# S5_Communications.net
KiCad netlist of a schematic drawn in Altium Designer
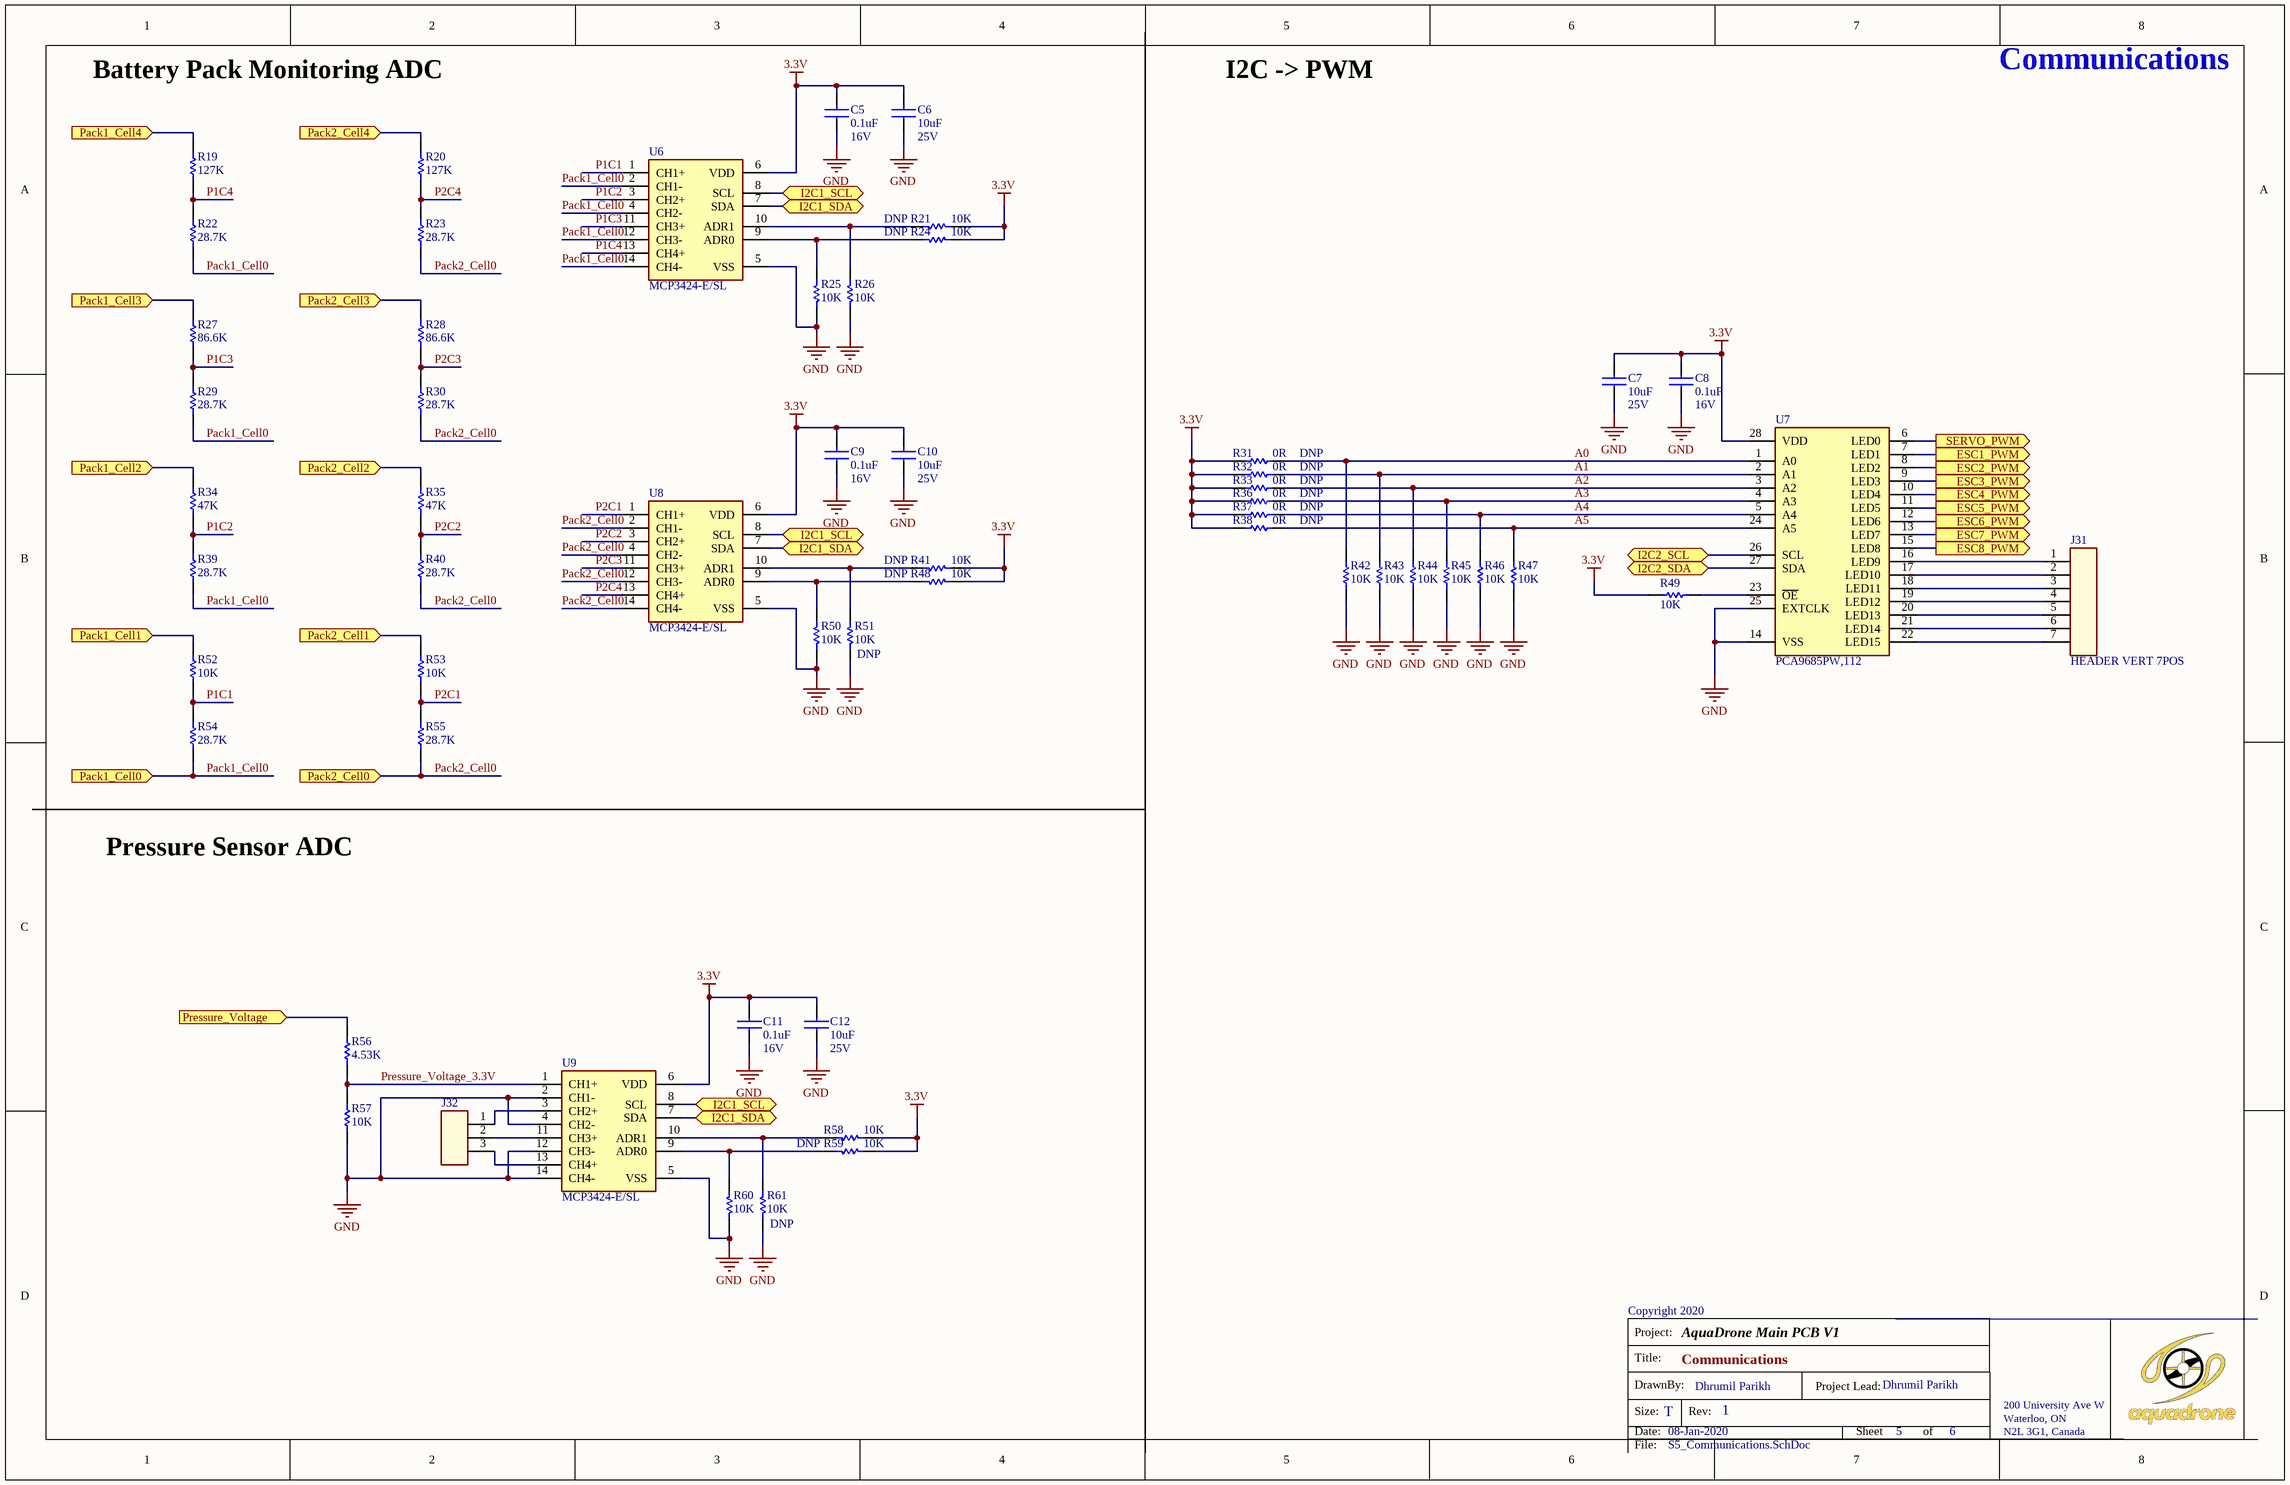
[diagram p0: S5_Communications.SchDoc]

(export (version "E")
  (design (tool "Eeschema 10.0.6"))
  (components
    (comp (ref "C5")
      (value "0.1uF")
      (footprint "RWMN:CAPC1608X09N")
      (description "CAP CER 0.1UF 16V X7R 0603")
      (fields
        (field (name "MFG") "KEMET")
        (field (name "MFG_PART_NO") "C0603C104M4RACTU")
        (field (name "VOLTAGE") "16V")
      )
      (libsource (lib "AquaDrone") (part "CAP CER 0.1UF 16V X7R 0603"))
    )
    (comp (ref "C6")
      (value "10uF")
      (footprint "RWMN:CAPC1608X09N")
      (description "CAP CER 10UF 25V X5R 0603")
      (fields
        (field (name "MFG") "KEMET")
        (field (name "MFG_PART_NO") "C1608X5R1E106M080AC")
        (field (name "VOLTAGE") "25V")
      )
      (libsource (lib "AquaDrone") (part "CAP CER 10UF 25V X5R 0603"))
    )
    (comp (ref "C7")
      (value "10uF")
      (footprint "RWMN:CAPC1608X09N")
      (description "CAP CER 10UF 25V X5R 0603")
      (fields
        (field (name "MFG") "KEMET")
        (field (name "MFG_PART_NO") "C1608X5R1E106M080AC")
        (field (name "VOLTAGE") "25V")
      )
      (libsource (lib "AquaDrone") (part "CAP CER 10UF 25V X5R 0603"))
    )
    (comp (ref "C8")
      (value "0.1uF")
      (footprint "RWMN:CAPC1608X09N")
      (description "CAP CER 0.1UF 16V X7R 0603")
      (fields
        (field (name "MFG") "KEMET")
        (field (name "MFG_PART_NO") "C0603C104M4RACTU")
        (field (name "VOLTAGE") "16V")
      )
      (libsource (lib "AquaDrone") (part "CAP CER 0.1UF 16V X7R 0603"))
    )
    (comp (ref "C9")
      (value "0.1uF")
      (footprint "RWMN:CAPC1608X09N")
      (description "CAP CER 0.1UF 16V X7R 0603")
      (fields
        (field (name "MFG") "KEMET")
        (field (name "MFG_PART_NO") "C0603C104M4RACTU")
        (field (name "VOLTAGE") "16V")
      )
      (libsource (lib "AquaDrone") (part "CAP CER 0.1UF 16V X7R 0603"))
    )
    (comp (ref "C10")
      (value "10uF")
      (footprint "RWMN:CAPC1608X09N")
      (description "CAP CER 10UF 25V X5R 0603")
      (fields
        (field (name "MFG") "KEMET")
        (field (name "MFG_PART_NO") "C1608X5R1E106M080AC")
        (field (name "VOLTAGE") "25V")
      )
      (libsource (lib "AquaDrone") (part "CAP CER 10UF 25V X5R 0603"))
    )
    (comp (ref "C11")
      (value "0.1uF")
      (footprint "RWMN:CAPC1608X09N")
      (description "CAP CER 0.1UF 16V X7R 0603")
      (fields
        (field (name "MFG") "KEMET")
        (field (name "MFG_PART_NO") "C0603C104M4RACTU")
        (field (name "VOLTAGE") "16V")
      )
      (libsource (lib "AquaDrone") (part "CAP CER 0.1UF 16V X7R 0603"))
    )
    (comp (ref "C12")
      (value "10uF")
      (footprint "RWMN:CAPC1608X09N")
      (description "CAP CER 10UF 25V X5R 0603")
      (fields
        (field (name "MFG") "KEMET")
        (field (name "MFG_PART_NO") "C1608X5R1E106M080AC")
        (field (name "VOLTAGE") "25V")
      )
      (libsource (lib "AquaDrone") (part "CAP CER 10UF 25V X5R 0603"))
    )
    (comp (ref "J31")
      (value "HEADER VERT 7POS")
      (footprint "61300711121")
      (description "CONN HEADER VERT 7POS 2.54MM")
      (fields (field (name "MFG") "Wurth Electronics Inc.") (field (name "MFG_PART_NO") "61300711121"))
      (libsource (lib "AquaDrone") (part "CONN HEADER VERT 7POS 2.54MM"))
    )
    (comp (ref "J32")
      (value "CONN HEADER VERT 3POS 2.54MM")
      (footprint "RWMN:61300311121")
      (fields (field (name "MFG") "Wurth Electronics Inc.") (field (name "MFG_PART_NO") "61300311121"))
      (libsource (lib "AquaDrone") (part "CONN HEADER VERT 3POS 2.54MM"))
    )
    (comp (ref "R19")
      (value "127K")
      (footprint "RESC1608X06N")
      (description "RES SMD 127K OHM 1% 1/10W 0603")
      (fields (field (name "MFG") "Vishay Dale") (field (name "MFG_PART_NO") "CRCW0603127KFKEA"))
      (libsource (lib "AquaDrone") (part "RES SMD 127K OHM 1% 1/10W 0603"))
    )
    (comp (ref "R20")
      (value "127K")
      (footprint "RESC1608X06N")
      (description "RES SMD 127K OHM 1% 1/10W 0603")
      (fields (field (name "MFG") "Vishay Dale") (field (name "MFG_PART_NO") "CRCW0603127KFKEA"))
      (libsource (lib "AquaDrone") (part "RES SMD 127K OHM 1% 1/10W 0603"))
    )
    (comp (ref "R21")
      (value "10K")
      (footprint "RESC1608X06N")
      (description "RES SMD 10K OHM 1% 1/10W 0603")
      (fields
        (field (name "MFG") "Vishay Dale")
        (field (name "NOSTUFF") "DNP")
        (field (name "MFG_PART_NO") "CRCW060310K0FKEA")
      )
      (libsource (lib "AquaDrone") (part "RES SMD 10K OHM 1% 1/10W 0603"))
    )
    (comp (ref "R22")
      (value "28.7K")
      (footprint "RESC1608X06N")
      (description "RES SMD 28.7K OHM 1% 1/10W 0603")
      (fields (field (name "MFG") "Yageo") (field (name "MFG_PART_NO") "RC0603FR-0728K7L"))
      (libsource (lib "AquaDrone") (part "RES SMD 28.7K OHM 1% 1/10W 0603"))
    )
    (comp (ref "R23")
      (value "28.7K")
      (footprint "RESC1608X06N")
      (description "RES SMD 28.7K OHM 1% 1/10W 0603")
      (fields (field (name "MFG") "Yageo") (field (name "MFG_PART_NO") "RC0603FR-0728K7L"))
      (libsource (lib "AquaDrone") (part "RES SMD 28.7K OHM 1% 1/10W 0603"))
    )
    (comp (ref "R24")
      (value "10K")
      (footprint "RESC1608X06N")
      (description "RES SMD 10K OHM 1% 1/10W 0603")
      (fields
        (field (name "MFG") "Vishay Dale")
        (field (name "NOSTUFF") "DNP")
        (field (name "MFG_PART_NO") "CRCW060310K0FKEA")
      )
      (libsource (lib "AquaDrone") (part "RES SMD 10K OHM 1% 1/10W 0603"))
    )
    (comp (ref "R25")
      (value "10K")
      (footprint "RESC1608X06N")
      (description "RES SMD 10K OHM 1% 1/10W 0603")
      (fields (field (name "MFG") "Vishay Dale") (field (name "MFG_PART_NO") "CRCW060310K0FKEA"))
      (libsource (lib "AquaDrone") (part "RES SMD 10K OHM 1% 1/10W 0603"))
    )
    (comp (ref "R26")
      (value "10K")
      (footprint "RESC1608X06N")
      (description "RES SMD 10K OHM 1% 1/10W 0603")
      (fields (field (name "MFG") "Vishay Dale") (field (name "MFG_PART_NO") "CRCW060310K0FKEA"))
      (libsource (lib "AquaDrone") (part "RES SMD 10K OHM 1% 1/10W 0603"))
    )
    (comp (ref "R27")
      (value "86.6K")
      (footprint "RESC1608X06N")
      (description "RES SMD 86.6K OHM 1% 1/10W 0603")
      (fields (field (name "MFG") "Yageo") (field (name "MFG_PART_NO") "RC0603FR-0786K6L"))
      (libsource (lib "AquaDrone") (part "RES SMD 86.6K OHM 1% 1/10W 0603"))
    )
    (comp (ref "R28")
      (value "86.6K")
      (footprint "RESC1608X06N")
      (description "RES SMD 86.6K OHM 1% 1/10W 0603")
      (fields (field (name "MFG") "Yageo") (field (name "MFG_PART_NO") "RC0603FR-0786K6L"))
      (libsource (lib "AquaDrone") (part "RES SMD 86.6K OHM 1% 1/10W 0603"))
    )
    (comp (ref "R29")
      (value "28.7K")
      (footprint "RESC1608X06N")
      (description "RES SMD 28.7K OHM 1% 1/10W 0603")
      (fields (field (name "MFG") "Yageo") (field (name "MFG_PART_NO") "RC0603FR-0728K7L"))
      (libsource (lib "AquaDrone") (part "RES SMD 28.7K OHM 1% 1/10W 0603"))
    )
    (comp (ref "R30")
      (value "28.7K")
      (footprint "RESC1608X06N")
      (description "RES SMD 28.7K OHM 1% 1/10W 0603")
      (fields (field (name "MFG") "Yageo") (field (name "MFG_PART_NO") "RC0603FR-0728K7L"))
      (libsource (lib "AquaDrone") (part "RES SMD 28.7K OHM 1% 1/10W 0603"))
    )
    (comp (ref "R31")
      (value "0R")
      (footprint "RESC2012X07N")
      (description "RES SMD 0 OHM JUMPER 1/8W 0805")
      (fields
        (field (name "MFG") "Panasonic")
        (field (name "NOSTUFF") "DNP")
        (field (name "MFG_PART_NO") "ERJ-6GEY0R00V")
      )
      (libsource (lib "AquaDrone") (part "RES SMD 0 OHM JUMPER 1/8W 0805"))
    )
    (comp (ref "R32")
      (value "0R")
      (footprint "RESC2012X07N")
      (description "RES SMD 0 OHM JUMPER 1/8W 0805")
      (fields
        (field (name "MFG") "Panasonic")
        (field (name "NOSTUFF") "DNP")
        (field (name "MFG_PART_NO") "ERJ-6GEY0R00V")
      )
      (libsource (lib "AquaDrone") (part "RES SMD 0 OHM JUMPER 1/8W 0805"))
    )
    (comp (ref "R33")
      (value "0R")
      (footprint "RESC2012X07N")
      (description "RES SMD 0 OHM JUMPER 1/8W 0805")
      (fields
        (field (name "MFG") "Panasonic")
        (field (name "NOSTUFF") "DNP")
        (field (name "MFG_PART_NO") "ERJ-6GEY0R00V")
      )
      (libsource (lib "AquaDrone") (part "RES SMD 0 OHM JUMPER 1/8W 0805"))
    )
    (comp (ref "R34")
      (value "47K")
      (footprint "RESC1608X06N")
      (description "RES SMD 47K OHM 1% 1/10W 0603")
      (fields (field (name "MFG") "Yageo") (field (name "MFG_PART_NO") "RC0603FR-0747KL"))
      (libsource (lib "AquaDrone") (part "RES SMD 47K OHM 1% 1/10W 0603"))
    )
    (comp (ref "R35")
      (value "47K")
      (footprint "RESC1608X06N")
      (description "RES SMD 47K OHM 1% 1/10W 0603")
      (fields (field (name "MFG") "Yageo") (field (name "MFG_PART_NO") "RC0603FR-0747KL"))
      (libsource (lib "AquaDrone") (part "RES SMD 47K OHM 1% 1/10W 0603"))
    )
    (comp (ref "R36")
      (value "0R")
      (footprint "RESC2012X07N")
      (description "RES SMD 0 OHM JUMPER 1/8W 0805")
      (fields
        (field (name "MFG") "Panasonic")
        (field (name "NOSTUFF") "DNP")
        (field (name "MFG_PART_NO") "ERJ-6GEY0R00V")
      )
      (libsource (lib "AquaDrone") (part "RES SMD 0 OHM JUMPER 1/8W 0805"))
    )
    (comp (ref "R37")
      (value "0R")
      (footprint "RESC2012X07N")
      (description "RES SMD 0 OHM JUMPER 1/8W 0805")
      (fields
        (field (name "MFG") "Panasonic")
        (field (name "NOSTUFF") "DNP")
        (field (name "MFG_PART_NO") "ERJ-6GEY0R00V")
      )
      (libsource (lib "AquaDrone") (part "RES SMD 0 OHM JUMPER 1/8W 0805"))
    )
    (comp (ref "R38")
      (value "0R")
      (footprint "RESC2012X07N")
      (description "RES SMD 0 OHM JUMPER 1/8W 0805")
      (fields
        (field (name "MFG") "Panasonic")
        (field (name "NOSTUFF") "DNP")
        (field (name "MFG_PART_NO") "ERJ-6GEY0R00V")
      )
      (libsource (lib "AquaDrone") (part "RES SMD 0 OHM JUMPER 1/8W 0805"))
    )
    (comp (ref "R39")
      (value "28.7K")
      (footprint "RESC1608X06N")
      (description "RES SMD 28.7K OHM 1% 1/10W 0603")
      (fields (field (name "MFG") "Yageo") (field (name "MFG_PART_NO") "RC0603FR-0728K7L"))
      (libsource (lib "AquaDrone") (part "RES SMD 28.7K OHM 1% 1/10W 0603"))
    )
    (comp (ref "R40")
      (value "28.7K")
      (footprint "RESC1608X06N")
      (description "RES SMD 28.7K OHM 1% 1/10W 0603")
      (fields (field (name "MFG") "Yageo") (field (name "MFG_PART_NO") "RC0603FR-0728K7L"))
      (libsource (lib "AquaDrone") (part "RES SMD 28.7K OHM 1% 1/10W 0603"))
    )
    (comp (ref "R41")
      (value "10K")
      (footprint "RESC1608X06N")
      (description "RES SMD 10K OHM 1% 1/10W 0603")
      (fields
        (field (name "MFG") "Vishay Dale")
        (field (name "NOSTUFF") "DNP")
        (field (name "MFG_PART_NO") "CRCW060310K0FKEA")
      )
      (libsource (lib "AquaDrone") (part "RES SMD 10K OHM 1% 1/10W 0603"))
    )
    (comp (ref "R42")
      (value "10K")
      (footprint "RESC1608X06N")
      (description "RES SMD 10K OHM 1% 1/10W 0603")
      (fields (field (name "MFG") "Vishay Dale") (field (name "MFG_PART_NO") "CRCW060310K0FKEA"))
      (libsource (lib "AquaDrone") (part "RES SMD 10K OHM 1% 1/10W 0603"))
    )
    (comp (ref "R43")
      (value "10K")
      (footprint "RESC1608X06N")
      (description "RES SMD 10K OHM 1% 1/10W 0603")
      (fields (field (name "MFG") "Vishay Dale") (field (name "MFG_PART_NO") "CRCW060310K0FKEA"))
      (libsource (lib "AquaDrone") (part "RES SMD 10K OHM 1% 1/10W 0603"))
    )
    (comp (ref "R44")
      (value "10K")
      (footprint "RESC1608X06N")
      (description "RES SMD 10K OHM 1% 1/10W 0603")
      (fields (field (name "MFG") "Vishay Dale") (field (name "MFG_PART_NO") "CRCW060310K0FKEA"))
      (libsource (lib "AquaDrone") (part "RES SMD 10K OHM 1% 1/10W 0603"))
    )
    (comp (ref "R45")
      (value "10K")
      (footprint "RESC1608X06N")
      (description "RES SMD 10K OHM 1% 1/10W 0603")
      (fields (field (name "MFG") "Vishay Dale") (field (name "MFG_PART_NO") "CRCW060310K0FKEA"))
      (libsource (lib "AquaDrone") (part "RES SMD 10K OHM 1% 1/10W 0603"))
    )
    (comp (ref "R46")
      (value "10K")
      (footprint "RESC1608X06N")
      (description "RES SMD 10K OHM 1% 1/10W 0603")
      (fields (field (name "MFG") "Vishay Dale") (field (name "MFG_PART_NO") "CRCW060310K0FKEA"))
      (libsource (lib "AquaDrone") (part "RES SMD 10K OHM 1% 1/10W 0603"))
    )
    (comp (ref "R47")
      (value "10K")
      (footprint "RESC1608X06N")
      (description "RES SMD 10K OHM 1% 1/10W 0603")
      (fields (field (name "MFG") "Vishay Dale") (field (name "MFG_PART_NO") "CRCW060310K0FKEA"))
      (libsource (lib "AquaDrone") (part "RES SMD 10K OHM 1% 1/10W 0603"))
    )
    (comp (ref "R48")
      (value "10K")
      (footprint "RESC1608X06N")
      (description "RES SMD 10K OHM 1% 1/10W 0603")
      (fields
        (field (name "MFG") "Vishay Dale")
        (field (name "NOSTUFF") "DNP")
        (field (name "MFG_PART_NO") "CRCW060310K0FKEA")
      )
      (libsource (lib "AquaDrone") (part "RES SMD 10K OHM 1% 1/10W 0603"))
    )
    (comp (ref "R49")
      (value "10K")
      (footprint "RESC1608X06N")
      (description "RES SMD 10K OHM 1% 1/10W 0603")
      (fields (field (name "MFG") "Vishay Dale") (field (name "MFG_PART_NO") "CRCW060310K0FKEA"))
      (libsource (lib "AquaDrone") (part "RES SMD 10K OHM 1% 1/10W 0603"))
    )
    (comp (ref "R50")
      (value "10K")
      (footprint "RESC1608X06N")
      (description "RES SMD 10K OHM 1% 1/10W 0603")
      (fields (field (name "MFG") "Vishay Dale") (field (name "MFG_PART_NO") "CRCW060310K0FKEA"))
      (libsource (lib "AquaDrone") (part "RES SMD 10K OHM 1% 1/10W 0603"))
    )
    (comp (ref "R51")
      (value "10K")
      (footprint "RESC1608X06N")
      (description "RES SMD 10K OHM 1% 1/10W 0603")
      (fields
        (field (name "MFG") "Vishay Dale")
        (field (name "NOSTUFF") "DNP")
        (field (name "MFG_PART_NO") "CRCW060310K0FKEA")
      )
      (libsource (lib "AquaDrone") (part "RES SMD 10K OHM 1% 1/10W 0603"))
    )
    (comp (ref "R52")
      (value "10K")
      (footprint "RESC1608X06N")
      (description "RES SMD 10K OHM 1% 1/10W 0603")
      (fields (field (name "MFG") "Vishay Dale") (field (name "MFG_PART_NO") "CRCW060310K0FKEA"))
      (libsource (lib "AquaDrone") (part "RES SMD 10K OHM 1% 1/10W 0603"))
    )
    (comp (ref "R53")
      (value "10K")
      (footprint "RESC1608X06N")
      (description "RES SMD 10K OHM 1% 1/10W 0603")
      (fields (field (name "MFG") "Vishay Dale") (field (name "MFG_PART_NO") "CRCW060310K0FKEA"))
      (libsource (lib "AquaDrone") (part "RES SMD 10K OHM 1% 1/10W 0603"))
    )
    (comp (ref "R54")
      (value "28.7K")
      (footprint "RESC1608X06N")
      (description "RES SMD 28.7K OHM 1% 1/10W 0603")
      (fields (field (name "MFG") "Yageo") (field (name "MFG_PART_NO") "RC0603FR-0728K7L"))
      (libsource (lib "AquaDrone") (part "RES SMD 28.7K OHM 1% 1/10W 0603"))
    )
    (comp (ref "R55")
      (value "28.7K")
      (footprint "RESC1608X06N")
      (description "RES SMD 28.7K OHM 1% 1/10W 0603")
      (fields (field (name "MFG") "Yageo") (field (name "MFG_PART_NO") "RC0603FR-0728K7L"))
      (libsource (lib "AquaDrone") (part "RES SMD 28.7K OHM 1% 1/10W 0603"))
    )
    (comp (ref "R56")
      (value "4.53K")
      (footprint "RESC1608X06N")
      (description "RES SMD 4.53K OHM 1% 1/10W 0603")
      (fields (field (name "MFG") "Yageo") (field (name "MFG_PART_NO") "RC0603FR-074K53L"))
      (libsource (lib "AquaDrone") (part "RES SMD 4.53K OHM 1% 1/10W 0603"))
    )
    (comp (ref "R57")
      (value "10K")
      (footprint "RESC1608X06N")
      (description "RES SMD 10K OHM 1% 1/10W 0603")
      (fields (field (name "MFG") "Vishay Dale") (field (name "MFG_PART_NO") "CRCW060310K0FKEA"))
      (libsource (lib "AquaDrone") (part "RES SMD 10K OHM 1% 1/10W 0603"))
    )
    (comp (ref "R58")
      (value "10K")
      (footprint "RESC1608X06N")
      (description "RES SMD 10K OHM 1% 1/10W 0603")
      (fields (field (name "MFG") "Vishay Dale") (field (name "MFG_PART_NO") "CRCW060310K0FKEA"))
      (libsource (lib "AquaDrone") (part "RES SMD 10K OHM 1% 1/10W 0603"))
    )
    (comp (ref "R59")
      (value "10K")
      (footprint "RESC1608X06N")
      (description "RES SMD 10K OHM 1% 1/10W 0603")
      (fields
        (field (name "MFG") "Vishay Dale")
        (field (name "NOSTUFF") "DNP")
        (field (name "MFG_PART_NO") "CRCW060310K0FKEA")
      )
      (libsource (lib "AquaDrone") (part "RES SMD 10K OHM 1% 1/10W 0603"))
    )
    (comp (ref "R60")
      (value "10K")
      (footprint "RESC1608X06N")
      (description "RES SMD 10K OHM 1% 1/10W 0603")
      (fields (field (name "MFG") "Vishay Dale") (field (name "MFG_PART_NO") "CRCW060310K0FKEA"))
      (libsource (lib "AquaDrone") (part "RES SMD 10K OHM 1% 1/10W 0603"))
    )
    (comp (ref "R61")
      (value "10K")
      (footprint "RESC1608X06N")
      (description "RES SMD 10K OHM 1% 1/10W 0603")
      (fields
        (field (name "MFG") "Vishay Dale")
        (field (name "NOSTUFF") "DNP")
        (field (name "MFG_PART_NO") "CRCW060310K0FKEA")
      )
      (libsource (lib "AquaDrone") (part "RES SMD 10K OHM 1% 1/10W 0603"))
    )
    (comp (ref "U6")
      (value "IC ADC 18BIT SIGMA-DELTA 14SOIC")
      (footprint "SOIC127P600X175-14N")
      (fields (field (name "MFG") "Microchip Technology") (field (name "MFG_PART_NO") "MCP3424-E/SL"))
      (libsource (lib "AquaDrone") (part "IC ADC 18BIT SIGMA-DELTA 14SOIC"))
    )
    (comp (ref "U7")
      (value "IC LED DRVR LIN DIM 25MA 28TSSOP")
      (footprint "SOP65P640X110-28N")
      (fields (field (name "MFG") "NXP USA Inc.") (field (name "MFG_PART_NO") "PCA9685PW,112"))
      (libsource (lib "AquaDrone") (part "IC LED DRVR LIN DIM 25MA 28TSSOP"))
    )
    (comp (ref "U8")
      (value "IC ADC 18BIT SIGMA-DELTA 14SOIC")
      (footprint "SOIC127P600X175-14N")
      (fields (field (name "MFG") "Microchip Technology") (field (name "MFG_PART_NO") "MCP3424-E/SL"))
      (libsource (lib "AquaDrone") (part "IC ADC 18BIT SIGMA-DELTA 14SOIC"))
    )
    (comp (ref "U9")
      (value "IC ADC 18BIT SIGMA-DELTA 14SOIC")
      (footprint "SOIC127P600X175-14N")
      (fields (field (name "MFG") "Microchip Technology") (field (name "MFG_PART_NO") "MCP3424-E/SL"))
      (libsource (lib "AquaDrone") (part "IC ADC 18BIT SIGMA-DELTA 14SOIC"))
    )
  )
  (nets
    (net (code "1") (name "/A0") (class "Default")
      (node (ref "R31") (pin "2") (pinfunction "2_2") (pintype "passive"))
      (node (ref "R42") (pin "2") (pinfunction "2_2") (pintype "passive"))
      (node (ref "U7") (pin "1") (pinfunction "A0_1") (pintype "passive"))
    )
    (net (code "2") (name "/A1") (class "Default")
      (node (ref "R32") (pin "2") (pinfunction "2_2") (pintype "passive"))
      (node (ref "R43") (pin "2") (pinfunction "2_2") (pintype "passive"))
      (node (ref "U7") (pin "2") (pinfunction "A1_2") (pintype "passive"))
    )
    (net (code "3") (name "/A2") (class "Default")
      (node (ref "R33") (pin "2") (pinfunction "2_2") (pintype "passive"))
      (node (ref "R44") (pin "2") (pinfunction "2_2") (pintype "passive"))
      (node (ref "U7") (pin "3") (pinfunction "A2_3") (pintype "passive"))
    )
    (net (code "4") (name "/A3") (class "Default")
      (node (ref "R36") (pin "2") (pinfunction "2_2") (pintype "passive"))
      (node (ref "R45") (pin "2") (pinfunction "2_2") (pintype "passive"))
      (node (ref "U7") (pin "4") (pinfunction "A3_4") (pintype "passive"))
    )
    (net (code "5") (name "/A4") (class "Default")
      (node (ref "R37") (pin "2") (pinfunction "2_2") (pintype "passive"))
      (node (ref "R46") (pin "2") (pinfunction "2_2") (pintype "passive"))
      (node (ref "U7") (pin "5") (pinfunction "A4_5") (pintype "passive"))
    )
    (net (code "6") (name "/A5") (class "Default")
      (node (ref "R38") (pin "2") (pinfunction "2_2") (pintype "passive"))
      (node (ref "R47") (pin "2") (pinfunction "2_2") (pintype "passive"))
      (node (ref "U7") (pin "24") (pinfunction "A5_24") (pintype "passive"))
    )
    (net (code "7") (name "/ESC1_PWM") (class "Default")
      (node (ref "U7") (pin "7") (pinfunction "LED1_7") (pintype "passive"))
    )
    (net (code "8") (name "/ESC2_PWM") (class "Default")
      (node (ref "U7") (pin "8") (pinfunction "LED2_8") (pintype "passive"))
    )
    (net (code "9") (name "/ESC3_PWM") (class "Default")
      (node (ref "U7") (pin "9") (pinfunction "LED3_9") (pintype "passive"))
    )
    (net (code "10") (name "/ESC4_PWM") (class "Default")
      (node (ref "U7") (pin "10") (pinfunction "LED4_10") (pintype "passive"))
    )
    (net (code "11") (name "/ESC5_PWM") (class "Default")
      (node (ref "U7") (pin "11") (pinfunction "LED5_11") (pintype "passive"))
    )
    (net (code "12") (name "/ESC6_PWM") (class "Default")
      (node (ref "U7") (pin "12") (pinfunction "LED6_12") (pintype "passive"))
    )
    (net (code "13") (name "/ESC7_PWM") (class "Default")
      (node (ref "U7") (pin "13") (pinfunction "LED7_13") (pintype "passive"))
    )
    (net (code "14") (name "/ESC8_PWM") (class "Default")
      (node (ref "U7") (pin "15") (pinfunction "LED8_15") (pintype "passive"))
    )
    (net (code "15") (name "/I2C1_SCL") (class "Default")
      (node (ref "U6") (pin "8") (pinfunction "SCL_8") (pintype "passive"))
      (node (ref "U8") (pin "8") (pinfunction "SCL_8") (pintype "passive"))
      (node (ref "U9") (pin "8") (pinfunction "SCL_8") (pintype "passive"))
    )
    (net (code "16") (name "/I2C1_SDA") (class "Default")
      (node (ref "U6") (pin "7") (pinfunction "SDA_7") (pintype "passive"))
      (node (ref "U8") (pin "7") (pinfunction "SDA_7") (pintype "passive"))
      (node (ref "U9") (pin "7") (pinfunction "SDA_7") (pintype "passive"))
    )
    (net (code "17") (name "/I2C2_SCL") (class "Default")
      (node (ref "U7") (pin "26") (pinfunction "SCL_26") (pintype "passive"))
    )
    (net (code "18") (name "/I2C2_SDA") (class "Default")
      (node (ref "U7") (pin "27") (pinfunction "SDA_27") (pintype "passive"))
    )
    (net (code "19") (name "/P1C1") (class "Default")
      (node (ref "R52") (pin "1") (pinfunction "1_1") (pintype "passive"))
      (node (ref "R54") (pin "2") (pinfunction "2_2") (pintype "passive"))
      (node (ref "U6") (pin "1") (pinfunction "CH1+_1") (pintype "passive"))
    )
    (net (code "20") (name "/P1C2") (class "Default")
      (node (ref "R34") (pin "1") (pinfunction "1_1") (pintype "passive"))
      (node (ref "R39") (pin "2") (pinfunction "2_2") (pintype "passive"))
      (node (ref "U6") (pin "3") (pinfunction "CH2+_3") (pintype "passive"))
    )
    (net (code "21") (name "/P1C3") (class "Default")
      (node (ref "R27") (pin "1") (pinfunction "1_1") (pintype "passive"))
      (node (ref "R29") (pin "2") (pinfunction "2_2") (pintype "passive"))
      (node (ref "U6") (pin "11") (pinfunction "CH3+_11") (pintype "passive"))
    )
    (net (code "22") (name "/P1C4") (class "Default")
      (node (ref "R19") (pin "1") (pinfunction "1_1") (pintype "passive"))
      (node (ref "R22") (pin "2") (pinfunction "2_2") (pintype "passive"))
      (node (ref "U6") (pin "13") (pinfunction "CH4+_13") (pintype "passive"))
    )
    (net (code "23") (name "/P2C1") (class "Default")
      (node (ref "R53") (pin "1") (pinfunction "1_1") (pintype "passive"))
      (node (ref "R55") (pin "2") (pinfunction "2_2") (pintype "passive"))
      (node (ref "U8") (pin "1") (pinfunction "CH1+_1") (pintype "passive"))
    )
    (net (code "24") (name "/P2C2") (class "Default")
      (node (ref "R35") (pin "1") (pinfunction "1_1") (pintype "passive"))
      (node (ref "R40") (pin "2") (pinfunction "2_2") (pintype "passive"))
      (node (ref "U8") (pin "3") (pinfunction "CH2+_3") (pintype "passive"))
    )
    (net (code "25") (name "/P2C3") (class "Default")
      (node (ref "R28") (pin "1") (pinfunction "1_1") (pintype "passive"))
      (node (ref "R30") (pin "2") (pinfunction "2_2") (pintype "passive"))
      (node (ref "U8") (pin "11") (pinfunction "CH3+_11") (pintype "passive"))
    )
    (net (code "26") (name "/P2C4") (class "Default")
      (node (ref "R20") (pin "1") (pinfunction "1_1") (pintype "passive"))
      (node (ref "R23") (pin "2") (pinfunction "2_2") (pintype "passive"))
      (node (ref "U8") (pin "13") (pinfunction "CH4+_13") (pintype "passive"))
    )
    (net (code "27") (name "/Pack1_Cell0") (class "Default")
      (node (ref "R22") (pin "1") (pinfunction "1_1") (pintype "passive"))
      (node (ref "R29") (pin "1") (pinfunction "1_1") (pintype "passive"))
      (node (ref "R39") (pin "1") (pinfunction "1_1") (pintype "passive"))
      (node (ref "R54") (pin "1") (pinfunction "1_1") (pintype "passive"))
      (node (ref "U6") (pin "12") (pinfunction "CH3-_12") (pintype "passive"))
      (node (ref "U6") (pin "14") (pinfunction "CH4-_14") (pintype "passive"))
      (node (ref "U6") (pin "2") (pinfunction "CH1-_2") (pintype "passive"))
      (node (ref "U6") (pin "4") (pinfunction "CH2-_4") (pintype "passive"))
    )
    (net (code "28") (name "/Pack1_Cell1") (class "Default")
      (node (ref "R52") (pin "2") (pinfunction "2_2") (pintype "passive"))
    )
    (net (code "29") (name "/Pack1_Cell2") (class "Default")
      (node (ref "R34") (pin "2") (pinfunction "2_2") (pintype "passive"))
    )
    (net (code "30") (name "/Pack1_Cell3") (class "Default")
      (node (ref "R27") (pin "2") (pinfunction "2_2") (pintype "passive"))
    )
    (net (code "31") (name "/Pack1_Cell4") (class "Default")
      (node (ref "R19") (pin "2") (pinfunction "2_2") (pintype "passive"))
    )
    (net (code "32") (name "/Pack2_Cell0") (class "Default")
      (node (ref "R23") (pin "1") (pinfunction "1_1") (pintype "passive"))
      (node (ref "R30") (pin "1") (pinfunction "1_1") (pintype "passive"))
      (node (ref "R40") (pin "1") (pinfunction "1_1") (pintype "passive"))
      (node (ref "R55") (pin "1") (pinfunction "1_1") (pintype "passive"))
      (node (ref "U8") (pin "12") (pinfunction "CH3-_12") (pintype "passive"))
      (node (ref "U8") (pin "14") (pinfunction "CH4-_14") (pintype "passive"))
      (node (ref "U8") (pin "2") (pinfunction "CH1-_2") (pintype "passive"))
      (node (ref "U8") (pin "4") (pinfunction "CH2-_4") (pintype "passive"))
    )
    (net (code "33") (name "/Pack2_Cell1") (class "Default")
      (node (ref "R53") (pin "2") (pinfunction "2_2") (pintype "passive"))
    )
    (net (code "34") (name "/Pack2_Cell2") (class "Default")
      (node (ref "R35") (pin "2") (pinfunction "2_2") (pintype "passive"))
    )
    (net (code "35") (name "/Pack2_Cell3") (class "Default")
      (node (ref "R28") (pin "2") (pinfunction "2_2") (pintype "passive"))
    )
    (net (code "36") (name "/Pack2_Cell4") (class "Default")
      (node (ref "R20") (pin "2") (pinfunction "2_2") (pintype "passive"))
    )
    (net (code "37") (name "/Pressure_Voltage") (class "Default")
      (node (ref "R56") (pin "2") (pinfunction "2_2") (pintype "passive"))
    )
    (net (code "38") (name "/Pressure_Voltage_3.3V") (class "Default")
      (node (ref "R56") (pin "1") (pinfunction "1_1") (pintype "passive"))
      (node (ref "R57") (pin "2") (pinfunction "2_2") (pintype "passive"))
      (node (ref "U9") (pin "1") (pinfunction "CH1+_1") (pintype "passive"))
    )
    (net (code "39") (name "/SERVO_PWM") (class "Default")
      (node (ref "U7") (pin "6") (pinfunction "LED0_6") (pintype "passive"))
    )
    (net (code "40") (name "3.3V") (class "Default")
      (node (ref "C10") (pin "2") (pinfunction "2_2") (pintype "passive"))
      (node (ref "C11") (pin "2") (pinfunction "2_2") (pintype "passive"))
      (node (ref "C12") (pin "2") (pinfunction "2_2") (pintype "passive"))
      (node (ref "C5") (pin "2") (pinfunction "2_2") (pintype "passive"))
      (node (ref "C6") (pin "2") (pinfunction "2_2") (pintype "passive"))
      (node (ref "C7") (pin "2") (pinfunction "2_2") (pintype "passive"))
      (node (ref "C8") (pin "2") (pinfunction "2_2") (pintype "passive"))
      (node (ref "C9") (pin "2") (pinfunction "2_2") (pintype "passive"))
      (node (ref "R21") (pin "1") (pinfunction "1_1") (pintype "passive"))
      (node (ref "R24") (pin "1") (pinfunction "1_1") (pintype "passive"))
      (node (ref "R31") (pin "1") (pinfunction "1_1") (pintype "passive"))
      (node (ref "R32") (pin "1") (pinfunction "1_1") (pintype "passive"))
      (node (ref "R33") (pin "1") (pinfunction "1_1") (pintype "passive"))
      (node (ref "R36") (pin "1") (pinfunction "1_1") (pintype "passive"))
      (node (ref "R37") (pin "1") (pinfunction "1_1") (pintype "passive"))
      (node (ref "R38") (pin "1") (pinfunction "1_1") (pintype "passive"))
      (node (ref "R41") (pin "1") (pinfunction "1_1") (pintype "passive"))
      (node (ref "R48") (pin "1") (pinfunction "1_1") (pintype "passive"))
      (node (ref "R49") (pin "1") (pinfunction "1_1") (pintype "passive"))
      (node (ref "R58") (pin "1") (pinfunction "1_1") (pintype "passive"))
      (node (ref "R59") (pin "1") (pinfunction "1_1") (pintype "passive"))
      (node (ref "U6") (pin "6") (pinfunction "VDD_6") (pintype "power_in"))
      (node (ref "U7") (pin "28") (pinfunction "VDD_28") (pintype "passive"))
      (node (ref "U8") (pin "6") (pinfunction "VDD_6") (pintype "power_in"))
      (node (ref "U9") (pin "6") (pinfunction "VDD_6") (pintype "power_in"))
    )
    (net (code "41") (name "GND") (class "Default")
      (node (ref "C10") (pin "1") (pinfunction "1_1") (pintype "passive"))
      (node (ref "C11") (pin "1") (pinfunction "1_1") (pintype "passive"))
      (node (ref "C12") (pin "1") (pinfunction "1_1") (pintype "passive"))
      (node (ref "C5") (pin "1") (pinfunction "1_1") (pintype "passive"))
      (node (ref "C6") (pin "1") (pinfunction "1_1") (pintype "passive"))
      (node (ref "C7") (pin "1") (pinfunction "1_1") (pintype "passive"))
      (node (ref "C8") (pin "1") (pinfunction "1_1") (pintype "passive"))
      (node (ref "C9") (pin "1") (pinfunction "1_1") (pintype "passive"))
      (node (ref "R25") (pin "1") (pinfunction "1_1") (pintype "passive"))
      (node (ref "R26") (pin "1") (pinfunction "1_1") (pintype "passive"))
      (node (ref "R42") (pin "1") (pinfunction "1_1") (pintype "passive"))
      (node (ref "R43") (pin "1") (pinfunction "1_1") (pintype "passive"))
      (node (ref "R44") (pin "1") (pinfunction "1_1") (pintype "passive"))
      (node (ref "R45") (pin "1") (pinfunction "1_1") (pintype "passive"))
      (node (ref "R46") (pin "1") (pinfunction "1_1") (pintype "passive"))
      (node (ref "R47") (pin "1") (pinfunction "1_1") (pintype "passive"))
      (node (ref "R50") (pin "1") (pinfunction "1_1") (pintype "passive"))
      (node (ref "R51") (pin "1") (pinfunction "1_1") (pintype "passive"))
      (node (ref "R57") (pin "1") (pinfunction "1_1") (pintype "passive"))
      (node (ref "R60") (pin "1") (pinfunction "1_1") (pintype "passive"))
      (node (ref "R61") (pin "1") (pinfunction "1_1") (pintype "passive"))
      (node (ref "U6") (pin "5") (pinfunction "VSS_5") (pintype "power_in"))
      (node (ref "U7") (pin "14") (pinfunction "VSS_14") (pintype "passive"))
      (node (ref "U7") (pin "25") (pinfunction "EXTCLK_25") (pintype "passive"))
      (node (ref "U8") (pin "5") (pinfunction "VSS_5") (pintype "power_in"))
      (node (ref "U9") (pin "12") (pinfunction "CH3-_12") (pintype "passive"))
      (node (ref "U9") (pin "14") (pinfunction "CH4-_14") (pintype "passive"))
      (node (ref "U9") (pin "2") (pinfunction "CH1-_2") (pintype "passive"))
      (node (ref "U9") (pin "4") (pinfunction "CH2-_4") (pintype "passive"))
      (node (ref "U9") (pin "5") (pinfunction "VSS_5") (pintype "power_in"))
    )
    (net (code "42") (name "Net-(U6-ADR0)") (class "Default")
      (node (ref "R24") (pin "2") (pinfunction "2_2") (pintype "passive"))
      (node (ref "R25") (pin "2") (pinfunction "2_2") (pintype "passive"))
      (node (ref "U6") (pin "9") (pinfunction "ADR0_9") (pintype "passive"))
    )
    (net (code "43") (name "Net-(U6-ADR1)") (class "Default")
      (node (ref "R21") (pin "2") (pinfunction "2_2") (pintype "passive"))
      (node (ref "R26") (pin "2") (pinfunction "2_2") (pintype "passive"))
      (node (ref "U6") (pin "10") (pinfunction "ADR1_10") (pintype "passive"))
    )
    (net (code "44") (name "Net-(U7-LED9)") (class "Default")
      (node (ref "J31") (pin "1") (pintype "passive"))
      (node (ref "U7") (pin "16") (pinfunction "LED9_16") (pintype "passive"))
    )
    (net (code "45") (name "Net-(U7-LED10)") (class "Default")
      (node (ref "J31") (pin "2") (pintype "passive"))
      (node (ref "U7") (pin "17") (pinfunction "LED10_17") (pintype "passive"))
    )
    (net (code "46") (name "Net-(U7-LED11)") (class "Default")
      (node (ref "J31") (pin "3") (pintype "passive"))
      (node (ref "U7") (pin "18") (pinfunction "LED11_18") (pintype "passive"))
    )
    (net (code "47") (name "Net-(U7-LED12)") (class "Default")
      (node (ref "J31") (pin "4") (pintype "passive"))
      (node (ref "U7") (pin "19") (pinfunction "LED12_19") (pintype "passive"))
    )
    (net (code "48") (name "Net-(U7-LED13)") (class "Default")
      (node (ref "J31") (pin "5") (pintype "passive"))
      (node (ref "U7") (pin "20") (pinfunction "LED13_20") (pintype "passive"))
    )
    (net (code "49") (name "Net-(U7-LED14)") (class "Default")
      (node (ref "J31") (pin "6") (pintype "passive"))
      (node (ref "U7") (pin "21") (pinfunction "LED14_21") (pintype "passive"))
    )
    (net (code "50") (name "Net-(U7-LED15)") (class "Default")
      (node (ref "J31") (pin "7") (pintype "passive"))
      (node (ref "U7") (pin "22") (pinfunction "LED15_22") (pintype "passive"))
    )
    (net (code "51") (name "Net-(U7-~{OE})") (class "Default")
      (node (ref "R49") (pin "2") (pinfunction "2_2") (pintype "passive"))
      (node (ref "U7") (pin "23") (pinfunction "~{OE}_23") (pintype "passive"))
    )
    (net (code "52") (name "Net-(U8-ADR0)") (class "Default")
      (node (ref "R48") (pin "2") (pinfunction "2_2") (pintype "passive"))
      (node (ref "R50") (pin "2") (pinfunction "2_2") (pintype "passive"))
      (node (ref "U8") (pin "9") (pinfunction "ADR0_9") (pintype "passive"))
    )
    (net (code "53") (name "Net-(U8-ADR1)") (class "Default")
      (node (ref "R41") (pin "2") (pinfunction "2_2") (pintype "passive"))
      (node (ref "R51") (pin "2") (pinfunction "2_2") (pintype "passive"))
      (node (ref "U8") (pin "10") (pinfunction "ADR1_10") (pintype "passive"))
    )
    (net (code "54") (name "Net-(U9-ADR0)") (class "Default")
      (node (ref "R59") (pin "2") (pinfunction "2_2") (pintype "passive"))
      (node (ref "R60") (pin "2") (pinfunction "2_2") (pintype "passive"))
      (node (ref "U9") (pin "9") (pinfunction "ADR0_9") (pintype "passive"))
    )
    (net (code "55") (name "Net-(U9-ADR1)") (class "Default")
      (node (ref "R58") (pin "2") (pinfunction "2_2") (pintype "passive"))
      (node (ref "R61") (pin "2") (pinfunction "2_2") (pintype "passive"))
      (node (ref "U9") (pin "10") (pinfunction "ADR1_10") (pintype "passive"))
    )
    (net (code "56") (name "Net-(U9-CH2+)") (class "Default")
      (node (ref "J32") (pin "1") (pintype "passive"))
      (node (ref "U9") (pin "3") (pinfunction "CH2+_3") (pintype "passive"))
    )
    (net (code "57") (name "Net-(U9-CH3+)") (class "Default")
      (node (ref "J32") (pin "2") (pintype "passive"))
      (node (ref "U9") (pin "11") (pinfunction "CH3+_11") (pintype "passive"))
    )
    (net (code "58") (name "Net-(U9-CH4+)") (class "Default")
      (node (ref "J32") (pin "3") (pintype "passive"))
      (node (ref "U9") (pin "13") (pinfunction "CH4+_13") (pintype "passive"))
    )
  )
)
